# through_hole_challenge.net
KiCad netlist of a schematic drawn in EAGLE
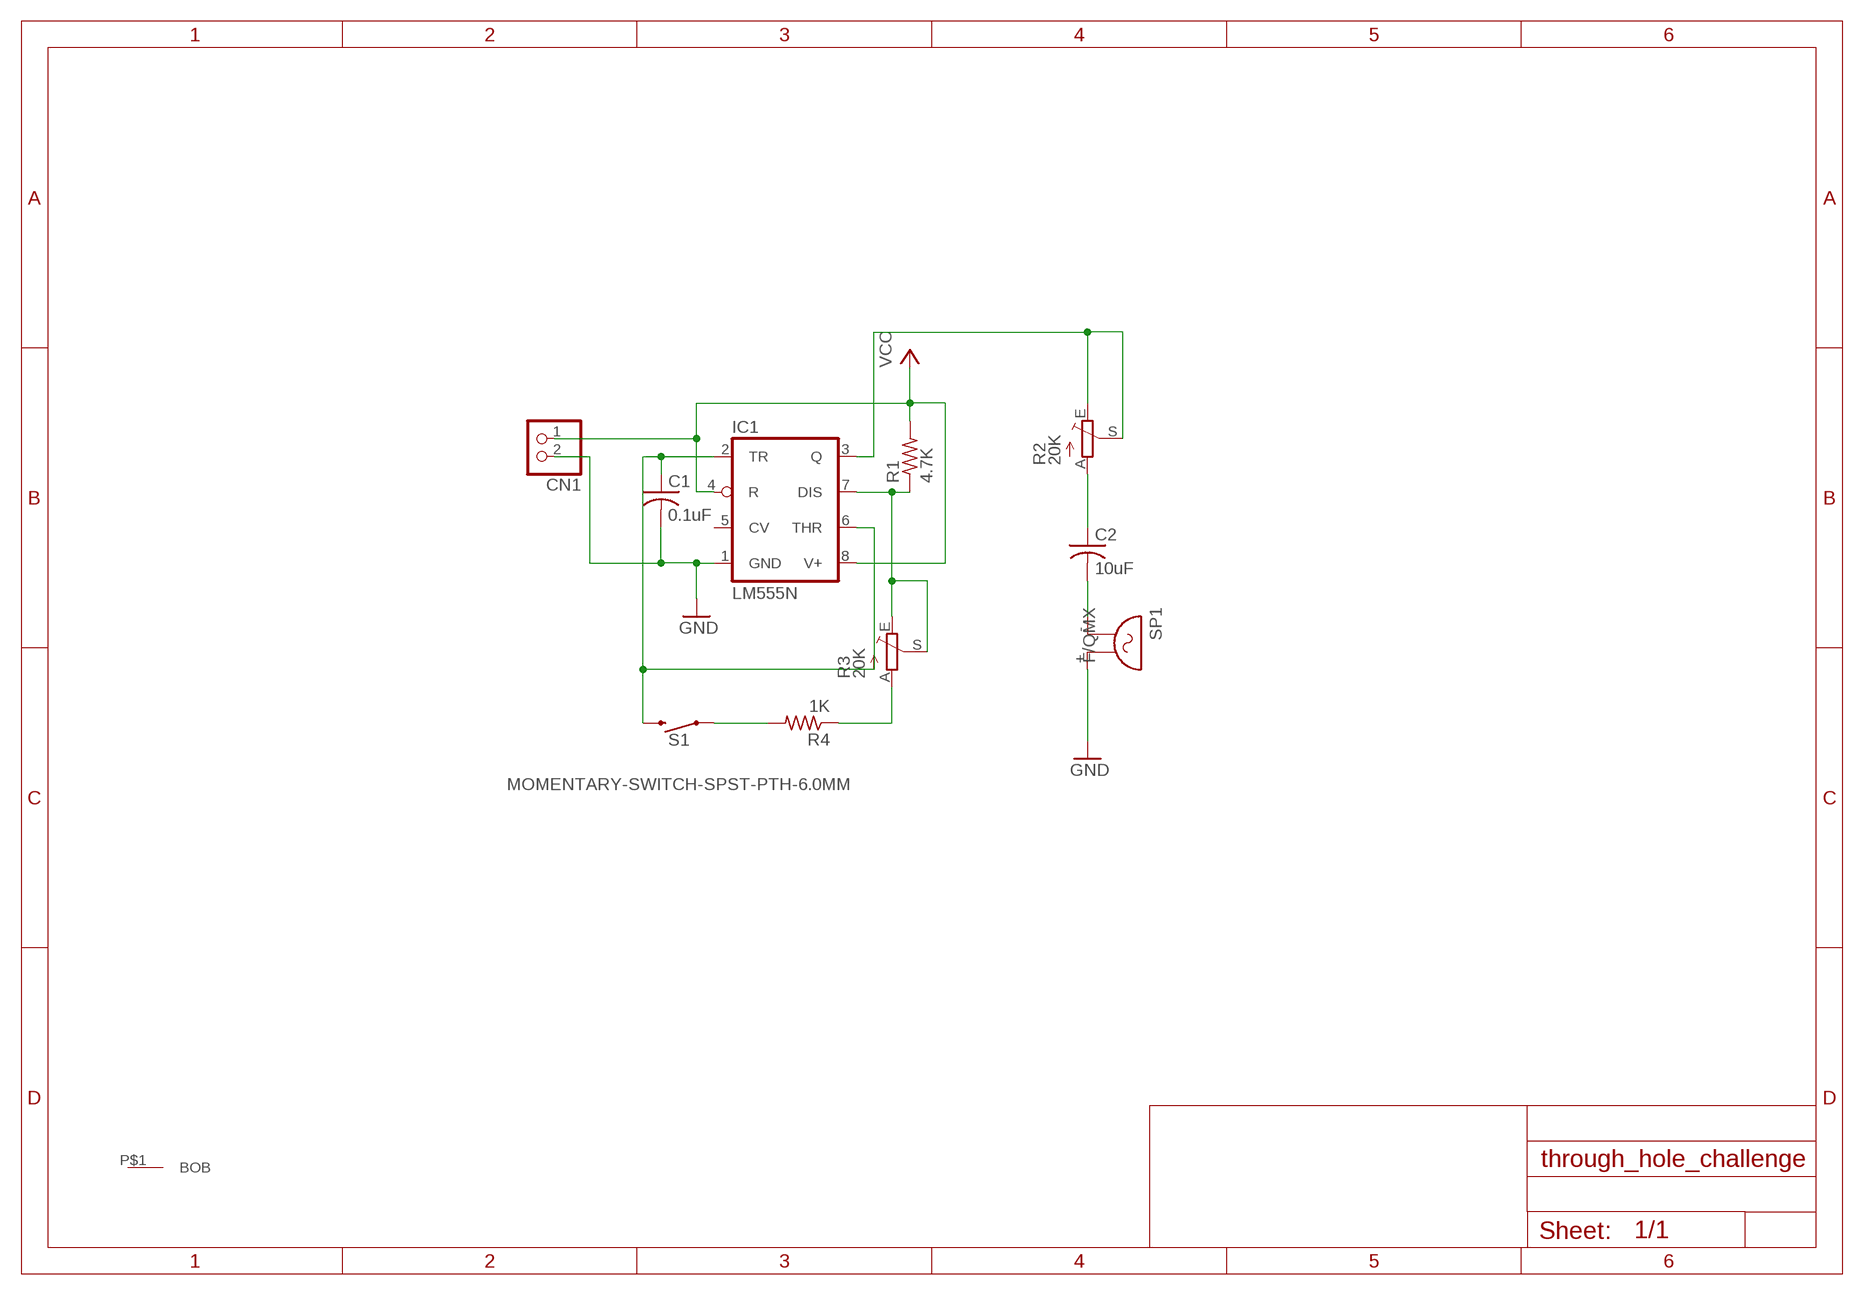
[diagram p0: schematic, sheet 1]

(export (version "E")
  (design (tool "Eeschema 10.0.6"))
  (components
    (comp (ref "C1")
      (value "0.1uF")
      (footprint "eagle-import:C050-035X075")
      (libsource (lib "eagle-import") (part "C-US050-035X075"))
    )
    (comp (ref "C2")
      (value "10uF")
      (footprint "eagle-import:C050-035X075")
      (libsource (lib "eagle-import") (part "C-US050-035X075"))
    )
    (comp (ref "CN1")
      (value "JST_2PIN-THM-RA")
      (footprint "eagle-import:JST-PH-2-THM-RA")
      (libsource (lib "eagle-import") (part "JST_2PIN-THM-RA"))
    )
    (comp (ref "IC1")
      (value "LM555N")
      (footprint "eagle-import:DIL08")
      (libsource (lib "eagle-import") (part "555NLM"))
    )
    (comp (ref "R1")
      (value "4.7K")
      (footprint "eagle-import:0207_9")
      (libsource (lib "eagle-import") (part "R-US_0207/9"))
    )
    (comp (ref "R2")
      (value "20K")
      (footprint "eagle-import:B25P")
      (libsource (lib "eagle-import") (part "TRIM_EU-B25P"))
    )
    (comp (ref "R3")
      (value "20K")
      (footprint "eagle-import:B25P")
      (libsource (lib "eagle-import") (part "TRIM_EU-B25P"))
    )
    (comp (ref "R4")
      (value "1K")
      (footprint "eagle-import:0207_9")
      (libsource (lib "eagle-import") (part "R-US_0207/9"))
    )
    (comp (ref "S1")
      (value "MOMENTARY-SWITCH-SPST-PTH-6.0MM")
      (footprint "eagle-import:TACTILE_SWITCH_PTH_6.0MM")
      (libsource (lib "eagle-import") (part "MOMENTARY-SWITCH-SPST-PTH-6.0MM"))
    )
    (comp (ref "SP1")
      (value "F/QMX")
      (footprint "eagle-import:F_QMX")
      (libsource (lib "eagle-import") (part "F/QMX"))
    )
    (comp (ref "U$1")
      (value "EEL_LOGO")
      (footprint "eagle-import:BOB_LOGO")
      (libsource (lib "eagle-import") (part "EEL_LOGO"))
    )
  )
  (nets
    (net (code "1") (name "GND") (class "Default")
      (node (ref "C1") (pin "2") (pinfunction "2_2") (pintype "passive"))
      (node (ref "CN1") (pin "2") (pinfunction "1_2") (pintype "passive"))
      (node (ref "IC1") (pin "1") (pinfunction "GND_1") (pintype "power_in"))
      (node (ref "SP1") (pin "+") (pinfunction "2_+") (pintype "passive"))
    )
    (net (code "2") (name "Net-(C2-Pad1)") (class "Default")
      (node (ref "C2") (pin "1") (pinfunction "1_1") (pintype "passive"))
      (node (ref "R2") (pin "A") (pinfunction "A_A") (pintype "passive"))
    )
    (net (code "3") (name "Net-(IC1-DIS)") (class "Default")
      (node (ref "IC1") (pin "7") (pinfunction "DIS_7") (pintype "input"))
      (node (ref "R1") (pin "1") (pinfunction "1_1") (pintype "passive"))
      (node (ref "R3") (pin "E") (pinfunction "E_E") (pintype "passive"))
      (node (ref "R3") (pin "S") (pinfunction "S_S") (pintype "passive"))
    )
    (net (code "4") (name "Net-(IC1-Q)") (class "Default")
      (node (ref "IC1") (pin "3") (pinfunction "Q_3") (pintype "output"))
      (node (ref "R2") (pin "E") (pinfunction "E_E") (pintype "passive"))
      (node (ref "R2") (pin "S") (pinfunction "S_S") (pintype "passive"))
    )
    (net (code "5") (name "Net-(IC1-THR)") (class "Default")
      (node (ref "C1") (pin "1") (pinfunction "1_1") (pintype "passive"))
      (node (ref "IC1") (pin "2") (pinfunction "TR_2") (pintype "input"))
      (node (ref "IC1") (pin "6") (pinfunction "THR_6") (pintype "input"))
      (node (ref "S1") (pin "3") (pinfunction "2_3") (pintype "passive"))
    )
    (net (code "6") (name "Net-(R3-PadA)") (class "Default")
      (node (ref "R3") (pin "A") (pinfunction "A_A") (pintype "passive"))
      (node (ref "R4") (pin "1") (pinfunction "1_1") (pintype "passive"))
    )
    (net (code "7") (name "Net-(R4-Pad2)") (class "Default")
      (node (ref "R4") (pin "2") (pinfunction "2_2") (pintype "passive"))
      (node (ref "S1") (pin "1") (pinfunction "1_1") (pintype "passive"))
    )
    (net (code "8") (name "Net-(SP1-1)") (class "Default")
      (node (ref "C2") (pin "2") (pinfunction "2_2") (pintype "passive"))
      (node (ref "SP1") (pin "-") (pinfunction "1_-") (pintype "passive"))
    )
    (net (code "9") (name "VCC") (class "Default")
      (node (ref "CN1") (pin "1") (pinfunction "2_1") (pintype "passive"))
      (node (ref "IC1") (pin "4") (pinfunction "R_4") (pintype "input"))
      (node (ref "IC1") (pin "8") (pinfunction "V+_8") (pintype "power_in"))
      (node (ref "R1") (pin "2") (pinfunction "2_2") (pintype "passive"))
    )
    (net (code "10") (name "unconnected-(IC1-CV-Pad5)") (class "Default")
      (node (ref "IC1") (pin "5") (pinfunction "CV_5") (pintype "input"))
    )
    (net (code "11") (name "unconnected-(U$1-BOB-PadP$1)") (class "Default")
      (node (ref "U$1") (pin "P$1") (pinfunction "BOB_P$1") (pintype "bidirectional"))
    )
  )
)
